# rumpus.net
KiCad netlist of a schematic drawn in EAGLE
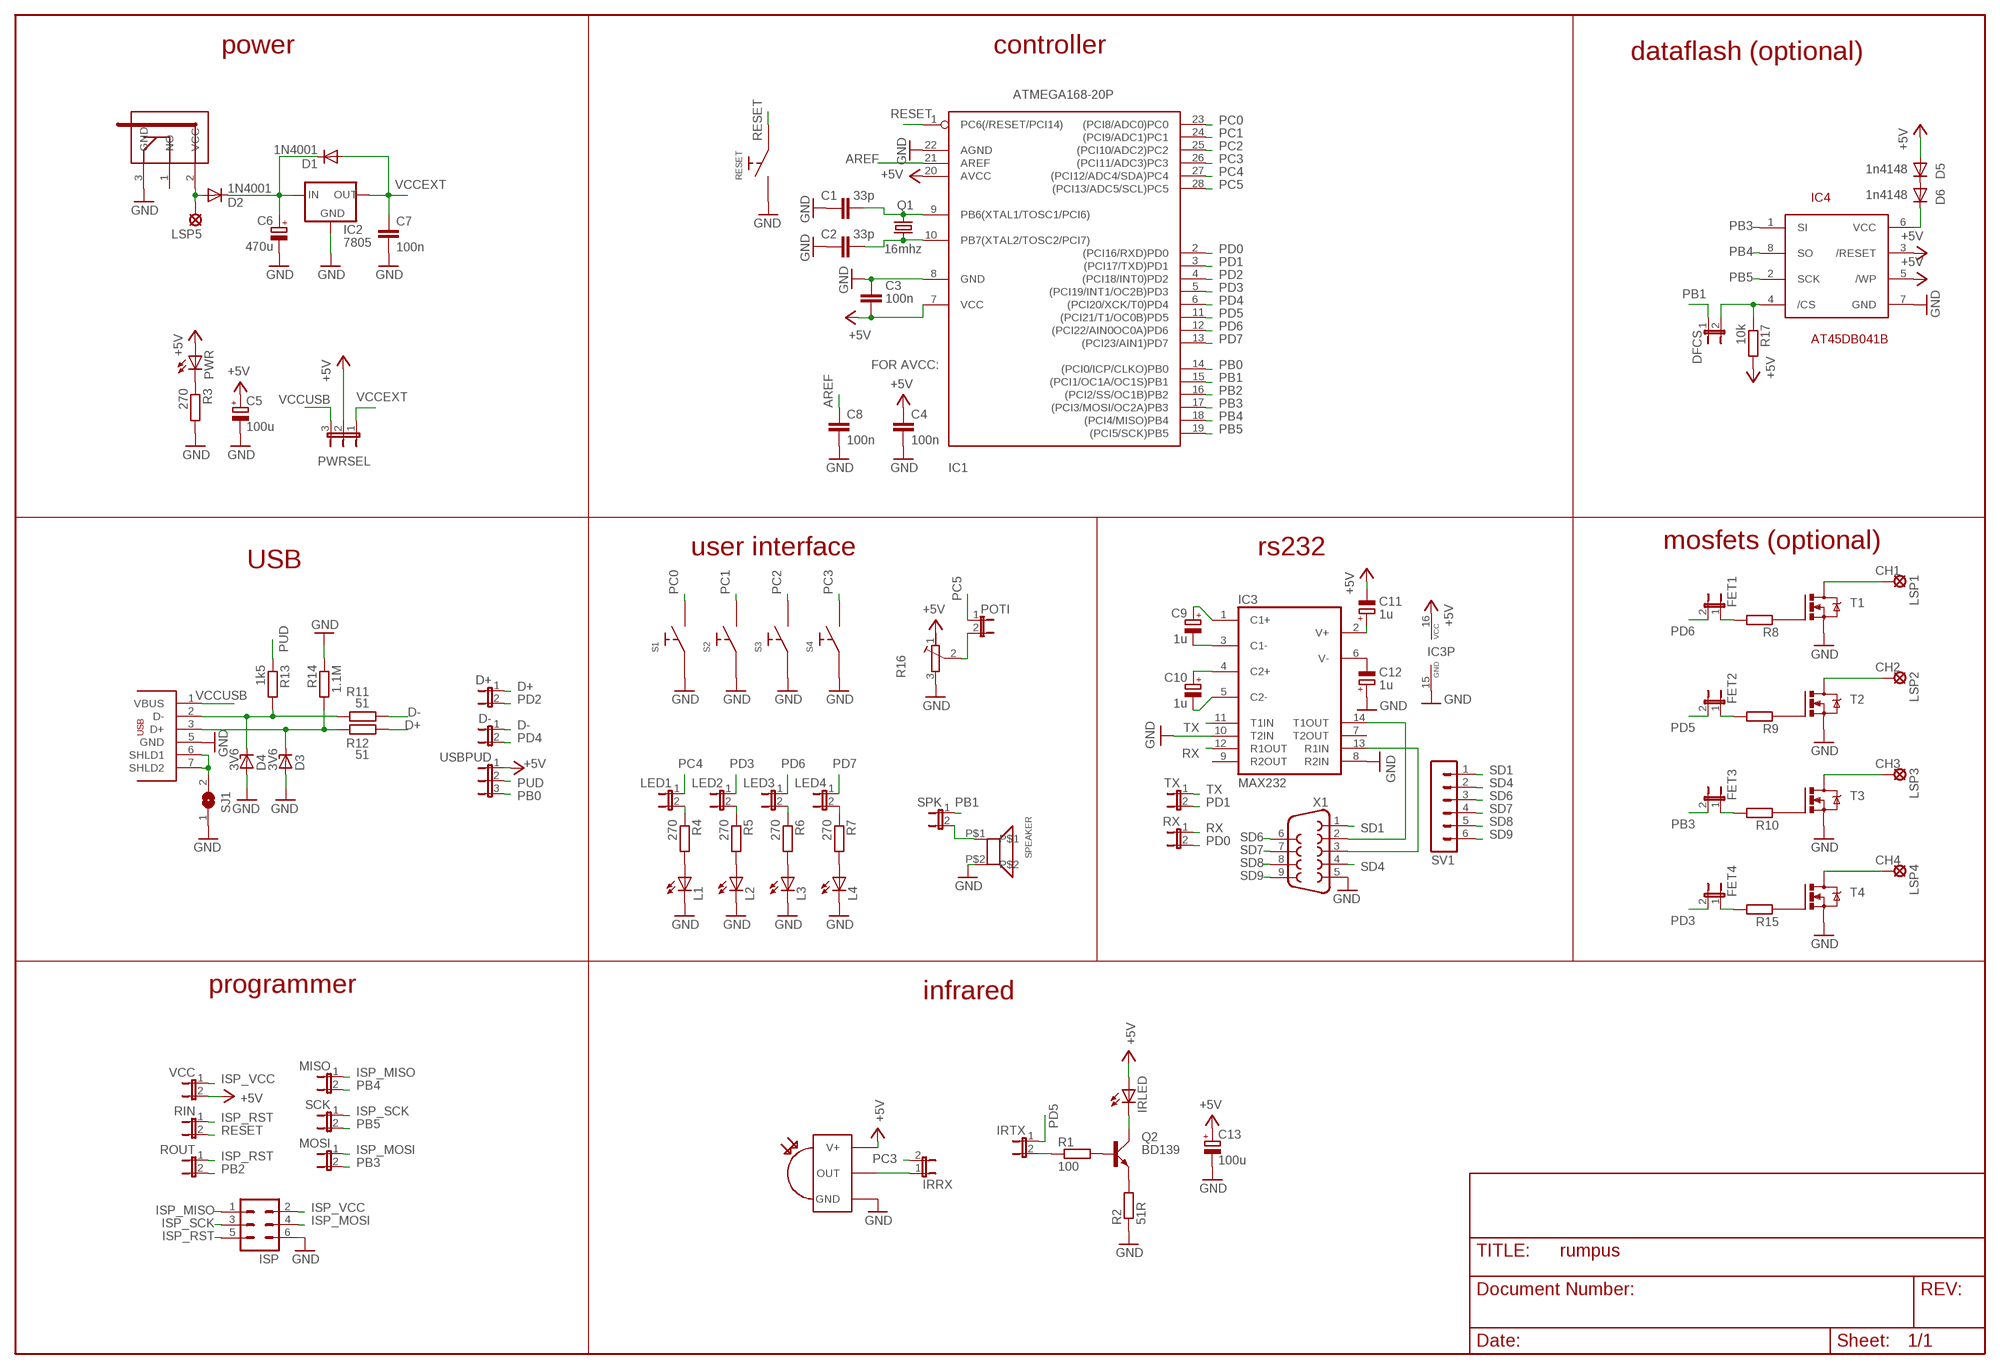
[diagram p0: schematic, sheet 1]

(export (version "E")
  (design (tool "Eeschema 10.0.6"))
  (components
    (comp (ref "C1")
      (value "33p")
      (footprint "eagle-import:C025-024X044")
      (libsource (lib "eagle-import") (part "C-EU025-024X044"))
    )
    (comp (ref "C2")
      (value "33p")
      (footprint "eagle-import:C025-024X044")
      (libsource (lib "eagle-import") (part "C-EU025-024X044"))
    )
    (comp (ref "C3")
      (value "100n")
      (footprint "eagle-import:C025-024X044")
      (libsource (lib "eagle-import") (part "C-EU025-024X044"))
    )
    (comp (ref "C4")
      (value "100n")
      (footprint "eagle-import:C025-024X044")
      (libsource (lib "eagle-import") (part "C-EU025-024X044"))
    )
    (comp (ref "C5")
      (value "100u")
      (footprint "eagle-import:E2,5-6")
      (libsource (lib "eagle-import") (part "CPOL-EUE2.5-6"))
    )
    (comp (ref "C6")
      (value "470u")
      (footprint "eagle-import:E5-10,5")
      (libsource (lib "eagle-import") (part "CPOL-EUE5-10.5"))
    )
    (comp (ref "C7")
      (value "100n")
      (footprint "eagle-import:C025-024X044")
      (libsource (lib "eagle-import") (part "C-EU025-024X044"))
    )
    (comp (ref "C8")
      (value "100n")
      (footprint "eagle-import:C025-024X044")
      (libsource (lib "eagle-import") (part "C-EU025-024X044"))
    )
    (comp (ref "C9")
      (value "1u")
      (footprint "eagle-import:E2,5-6")
      (libsource (lib "eagle-import") (part "CPOL-EUE2.5-6"))
    )
    (comp (ref "C10")
      (value "1u")
      (footprint "eagle-import:E2,5-6")
      (libsource (lib "eagle-import") (part "CPOL-EUE2.5-6"))
    )
    (comp (ref "C11")
      (value "1u")
      (footprint "eagle-import:E2,5-6")
      (libsource (lib "eagle-import") (part "CPOL-EUE2.5-6"))
    )
    (comp (ref "C12")
      (value "1u")
      (footprint "eagle-import:E2,5-6")
      (libsource (lib "eagle-import") (part "CPOL-EUE2.5-6"))
    )
    (comp (ref "C13")
      (value "100u")
      (footprint "eagle-import:E2,5-6")
      (libsource (lib "eagle-import") (part "CPOL-EUE2.5-6"))
    )
    (comp (ref "D+")
      (value "JP1E")
      (footprint "eagle-import:JP1")
      (libsource (lib "eagle-import") (part "JP1E"))
    )
    (comp (ref "D-")
      (value "JP1E")
      (footprint "eagle-import:JP1")
      (libsource (lib "eagle-import") (part "JP1E"))
    )
    (comp (ref "D1")
      (value "1N4001")
      (footprint "eagle-import:DO41-10")
      (libsource (lib "eagle-import") (part "1N4004"))
    )
    (comp (ref "D2")
      (value "1N4001")
      (footprint "eagle-import:DO41-10")
      (libsource (lib "eagle-import") (part "1N4004"))
    )
    (comp (ref "D3")
      (value "3V6")
      (footprint "eagle-import:ZDIO-2.5")
      (libsource (lib "eagle-import") (part "ZENER-DIODEZD-2.5"))
    )
    (comp (ref "D4")
      (value "3V6")
      (footprint "eagle-import:ZDIO-2.5")
      (libsource (lib "eagle-import") (part "ZENER-DIODEZD-2.5"))
    )
    (comp (ref "D5")
      (value "1n4148")
      (footprint "eagle-import:D-2.5")
      (libsource (lib "eagle-import") (part "DIODE-D-2.5"))
    )
    (comp (ref "D6")
      (value "1n4148")
      (footprint "eagle-import:D-2.5")
      (libsource (lib "eagle-import") (part "DIODE-D-2.5"))
    )
    (comp (ref "DFCS")
      (value "JP1E")
      (footprint "eagle-import:JP1")
      (libsource (lib "eagle-import") (part "JP1E"))
    )
    (comp (ref "FET1")
      (value "JP1E")
      (footprint "eagle-import:JP1")
      (libsource (lib "eagle-import") (part "JP1E"))
    )
    (comp (ref "FET2")
      (value "JP1E")
      (footprint "eagle-import:JP1")
      (libsource (lib "eagle-import") (part "JP1E"))
    )
    (comp (ref "FET3")
      (value "JP1E")
      (footprint "eagle-import:JP1")
      (libsource (lib "eagle-import") (part "JP1E"))
    )
    (comp (ref "FET4")
      (value "JP1E")
      (footprint "eagle-import:JP1")
      (libsource (lib "eagle-import") (part "JP1E"))
    )
    (comp (ref "IC1")
      (value "ATMEGA168-20P")
      (footprint "eagle-import:DIL28-3")
      (libsource (lib "eagle-import") (part "ATMEGA168P-20"))
    )
    (comp (ref "IC2")
      (value "7805")
      (footprint "eagle-import:78XXS")
      (libsource (lib "eagle-import") (part "78XXS"))
    )
    (comp (ref "IC3")
      (value "MAX232")
      (footprint "eagle-import:DIL16")
      (libsource (lib "eagle-import") (part "MAX232"))
    )
    (comp (ref "IC4")
      (value "AT45DB041B")
      (footprint "eagle-import:SOIC8")
      (libsource (lib "eagle-import") (part "AT45DB041B"))
    )
    (comp (ref "IRLED")
      (value "LED5MM")
      (footprint "eagle-import:LED5MM")
      (libsource (lib "eagle-import") (part "LED5MM"))
    )
    (comp (ref "IRRX")
      (value "JP1E")
      (footprint "eagle-import:JP1")
      (libsource (lib "eagle-import") (part "JP1E"))
    )
    (comp (ref "IRTX")
      (value "JP1E")
      (footprint "eagle-import:JP1")
      (libsource (lib "eagle-import") (part "JP1E"))
    )
    (comp (ref "ISP")
      (value "MA03-2")
      (footprint "eagle-import:MA03-2")
      (libsource (lib "eagle-import") (part "MA03-2"))
    )
    (comp (ref "L1")
      (value "LED3MM")
      (footprint "eagle-import:LED3MM")
      (libsource (lib "eagle-import") (part "LED3MM"))
    )
    (comp (ref "L2")
      (value "LED3MM")
      (footprint "eagle-import:LED3MM")
      (libsource (lib "eagle-import") (part "LED3MM"))
    )
    (comp (ref "L3")
      (value "LED3MM")
      (footprint "eagle-import:LED3MM")
      (libsource (lib "eagle-import") (part "LED3MM"))
    )
    (comp (ref "L4")
      (value "LED3MM")
      (footprint "eagle-import:LED3MM")
      (libsource (lib "eagle-import") (part "LED3MM"))
    )
    (comp (ref "LED1")
      (value "JP1E")
      (footprint "eagle-import:JP1")
      (libsource (lib "eagle-import") (part "JP1E"))
    )
    (comp (ref "LED2")
      (value "JP1E")
      (footprint "eagle-import:JP1")
      (libsource (lib "eagle-import") (part "JP1E"))
    )
    (comp (ref "LED3")
      (value "JP1E")
      (footprint "eagle-import:JP1")
      (libsource (lib "eagle-import") (part "JP1E"))
    )
    (comp (ref "LED4")
      (value "JP1E")
      (footprint "eagle-import:JP1")
      (libsource (lib "eagle-import") (part "JP1E"))
    )
    (comp (ref "LSP1")
      (value "LSP10")
      (footprint "eagle-import:LSP10")
      (libsource (lib "eagle-import") (part "LSP10"))
    )
    (comp (ref "LSP2")
      (value "LSP10")
      (footprint "eagle-import:LSP10")
      (libsource (lib "eagle-import") (part "LSP10"))
    )
    (comp (ref "LSP3")
      (value "LSP10")
      (footprint "eagle-import:LSP10")
      (libsource (lib "eagle-import") (part "LSP10"))
    )
    (comp (ref "LSP4")
      (value "LSP10")
      (footprint "eagle-import:LSP10")
      (libsource (lib "eagle-import") (part "LSP10"))
    )
    (comp (ref "LSP5")
      (value "LSP10")
      (footprint "eagle-import:LSP10")
      (libsource (lib "eagle-import") (part "LSP10"))
    )
    (comp (ref "MISO")
      (value "JP1E")
      (footprint "eagle-import:JP1")
      (libsource (lib "eagle-import") (part "JP1E"))
    )
    (comp (ref "MOSI")
      (value "JP1E")
      (footprint "eagle-import:JP1")
      (libsource (lib "eagle-import") (part "JP1E"))
    )
    (comp (ref "POTI")
      (value "JP1E")
      (footprint "eagle-import:JP1")
      (libsource (lib "eagle-import") (part "JP1E"))
    )
    (comp (ref "PWR")
      (value "LED3MM")
      (footprint "eagle-import:LED3MM")
      (libsource (lib "eagle-import") (part "LED3MM"))
    )
    (comp (ref "PWRSEL")
      (value "JP2E")
      (footprint "eagle-import:JP2")
      (libsource (lib "eagle-import") (part "JP2E"))
    )
    (comp (ref "Q1")
      (value "16mhz")
      (footprint "eagle-import:HC49U-V")
      (libsource (lib "eagle-import") (part "CRYTALHC49U-V"))
    )
    (comp (ref "Q2")
      (value "BD139")
      (footprint "eagle-import:TO126AV")
      (libsource (lib "eagle-import") (part "BD139"))
    )
    (comp (ref "R1")
      (value "100")
      (footprint "eagle-import:0204V")
      (libsource (lib "eagle-import") (part "R-EU_0204/2V"))
    )
    (comp (ref "R2")
      (value "51R")
      (footprint "eagle-import:0204V")
      (libsource (lib "eagle-import") (part "R-EU_0204/2V"))
    )
    (comp (ref "R3")
      (value "270")
      (footprint "eagle-import:0204_7")
      (libsource (lib "eagle-import") (part "R-EU_0204/7"))
    )
    (comp (ref "R4")
      (value "270")
      (footprint "eagle-import:0204V")
      (libsource (lib "eagle-import") (part "R-EU_0204/2V"))
    )
    (comp (ref "R5")
      (value "270")
      (footprint "eagle-import:0204V")
      (libsource (lib "eagle-import") (part "R-EU_0204/2V"))
    )
    (comp (ref "R6")
      (value "270")
      (footprint "eagle-import:0204V")
      (libsource (lib "eagle-import") (part "R-EU_0204/2V"))
    )
    (comp (ref "R7")
      (value "270")
      (footprint "eagle-import:0204V")
      (libsource (lib "eagle-import") (part "R-EU_0204/2V"))
    )
    (comp (ref "R8")
      (value "R-EU_0204/2V")
      (footprint "eagle-import:0204V")
      (libsource (lib "eagle-import") (part "R-EU_0204/2V"))
    )
    (comp (ref "R9")
      (value "R-EU_0204/2V")
      (footprint "eagle-import:0204V")
      (libsource (lib "eagle-import") (part "R-EU_0204/2V"))
    )
    (comp (ref "R10")
      (value "R-EU_0204/2V")
      (footprint "eagle-import:0204V")
      (libsource (lib "eagle-import") (part "R-EU_0204/2V"))
    )
    (comp (ref "R11")
      (value "51")
      (footprint "eagle-import:0204V")
      (libsource (lib "eagle-import") (part "R-EU_0204/2V"))
    )
    (comp (ref "R12")
      (value "51")
      (footprint "eagle-import:0204V")
      (libsource (lib "eagle-import") (part "R-EU_0204/2V"))
    )
    (comp (ref "R13")
      (value "1k5")
      (footprint "eagle-import:0204V")
      (libsource (lib "eagle-import") (part "R-EU_0204/2V"))
    )
    (comp (ref "R14")
      (value "1.1M")
      (footprint "eagle-import:0204V")
      (libsource (lib "eagle-import") (part "R-EU_0204/2V"))
    )
    (comp (ref "R15")
      (value "R-EU_0204/2V")
      (footprint "eagle-import:0204V")
      (libsource (lib "eagle-import") (part "R-EU_0204/2V"))
    )
    (comp (ref "R16")
      (value "R-TRIMMPT6-L")
      (footprint "eagle-import:PT6-L")
      (libsource (lib "eagle-import") (part "R-TRIMMPT6-L"))
    )
    (comp (ref "R17")
      (value "10k")
      (footprint "eagle-import:0204V")
      (libsource (lib "eagle-import") (part "R-EU_0204/2V"))
    )
    (comp (ref "RESET")
      (value "MIKROTASTER6X6L")
      (footprint "eagle-import:TASTER3301")
      (libsource (lib "eagle-import") (part "MIKROTASTER6X6L"))
    )
    (comp (ref "RIN")
      (value "JP1E")
      (footprint "eagle-import:JP1")
      (libsource (lib "eagle-import") (part "JP1E"))
    )
    (comp (ref "ROUT")
      (value "JP1E")
      (footprint "eagle-import:JP1")
      (libsource (lib "eagle-import") (part "JP1E"))
    )
    (comp (ref "RX")
      (value "JP1E")
      (footprint "eagle-import:JP1")
      (libsource (lib "eagle-import") (part "JP1E"))
    )
    (comp (ref "S1")
      (value "MIKROTASTER6X6L")
      (footprint "eagle-import:TASTER3301")
      (libsource (lib "eagle-import") (part "MIKROTASTER6X6L"))
    )
    (comp (ref "S2")
      (value "MIKROTASTER6X6L")
      (footprint "eagle-import:TASTER3301")
      (libsource (lib "eagle-import") (part "MIKROTASTER6X6L"))
    )
    (comp (ref "S3")
      (value "MIKROTASTER6X6L")
      (footprint "eagle-import:TASTER3301")
      (libsource (lib "eagle-import") (part "MIKROTASTER6X6L"))
    )
    (comp (ref "S4")
      (value "MIKROTASTER6X6L")
      (footprint "eagle-import:TASTER3301")
      (libsource (lib "eagle-import") (part "MIKROTASTER6X6L"))
    )
    (comp (ref "SCK")
      (value "JP1E")
      (footprint "eagle-import:JP1")
      (libsource (lib "eagle-import") (part "JP1E"))
    )
    (comp (ref "SJ1") (value "SJ") (footprint "eagle-import:SJ") (libsource (lib "eagle-import") (part "SJ")))
    (comp (ref "SPEAKER")
      (value "BUZZER")
      (footprint "eagle-import:BUZZER")
      (libsource (lib "eagle-import") (part "BUZZER"))
    )
    (comp (ref "SPK")
      (value "JP1E")
      (footprint "eagle-import:JP1")
      (libsource (lib "eagle-import") (part "JP1E"))
    )
    (comp (ref "SV1")
      (value "MA06-1")
      (footprint "eagle-import:MA06-1")
      (libsource (lib "eagle-import") (part "MA06-1"))
    )
    (comp (ref "T1")
      (value "N-CHANNEL-MOSFET")
      (footprint "eagle-import:TO220BV")
      (libsource (lib "eagle-import") (part "N-CHANNEL-MOSFET"))
    )
    (comp (ref "T2")
      (value "N-CHANNEL-MOSFET")
      (footprint "eagle-import:TO220BV")
      (libsource (lib "eagle-import") (part "N-CHANNEL-MOSFET"))
    )
    (comp (ref "T3")
      (value "N-CHANNEL-MOSFET")
      (footprint "eagle-import:TO220BV")
      (libsource (lib "eagle-import") (part "N-CHANNEL-MOSFET"))
    )
    (comp (ref "T4")
      (value "N-CHANNEL-MOSFET")
      (footprint "eagle-import:TO220BV")
      (libsource (lib "eagle-import") (part "N-CHANNEL-MOSFET"))
    )
    (comp (ref "TX")
      (value "JP1E")
      (footprint "eagle-import:JP1")
      (libsource (lib "eagle-import") (part "JP1E"))
    )
    (comp (ref "U$2")
      (value "TSOP1738")
      (footprint "eagle-import:TSOP17XX")
      (libsource (lib "eagle-import") (part "TSOP1738"))
    )
    (comp (ref "U$3")
      (value "HEBW21")
      (footprint "eagle-import:HEBW21")
      (libsource (lib "eagle-import") (part "HEBW21"))
    )
    (comp (ref "USB")
      (value "USB-SOCKETMINI-B")
      (footprint "eagle-import:USB-BWM")
      (libsource (lib "eagle-import") (part "USB-SOCKETMINI-B"))
    )
    (comp (ref "USBPUD")
      (value "JP2E")
      (footprint "eagle-import:JP2")
      (libsource (lib "eagle-import") (part "JP2E"))
    )
    (comp (ref "VCC")
      (value "JP1E")
      (footprint "eagle-import:JP1")
      (libsource (lib "eagle-import") (part "JP1E"))
    )
    (comp (ref "X1")
      (value "F09HP")
      (footprint "eagle-import:F09HP")
      (libsource (lib "eagle-import") (part "F09HP"))
    )
  )
  (nets
    (net (code "1") (name "+5V") (class "Default")
      (node (ref "C11") (pin "-") (pinfunction "-_-") (pintype "passive"))
      (node (ref "C13") (pin "+") (pinfunction "+_+") (pintype "passive"))
      (node (ref "C3") (pin "2") (pinfunction "2_2") (pintype "passive"))
      (node (ref "C4") (pin "1") (pinfunction "1_1") (pintype "passive"))
      (node (ref "C5") (pin "+") (pinfunction "+_+") (pintype "passive"))
      (node (ref "D5") (pin "A") (pinfunction "A_A") (pintype "passive"))
      (node (ref "IC1") (pin "20") (pinfunction "AVCC_20") (pintype "bidirectional"))
      (node (ref "IC1") (pin "7") (pinfunction "VCC_7") (pintype "bidirectional"))
      (node (ref "IC3") (pin "16") (pinfunction "VCC_16") (pintype "power_in"))
      (node (ref "IC4") (pin "3") (pinfunction "/RESET_3") (pintype "bidirectional"))
      (node (ref "IC4") (pin "5") (pinfunction "/WP_5") (pintype "bidirectional"))
      (node (ref "IRLED") (pin "A") (pinfunction "A_A") (pintype "passive"))
      (node (ref "PWR") (pin "A") (pinfunction "A_A") (pintype "passive"))
      (node (ref "PWRSEL") (pin "2") (pinfunction "2_2") (pintype "passive"))
      (node (ref "R16") (pin "1") (pinfunction "A_1") (pintype "passive"))
      (node (ref "R17") (pin "2") (pinfunction "2_2") (pintype "passive"))
      (node (ref "U$2") (pin "V+") (pinfunction "V+_V+") (pintype "bidirectional"))
      (node (ref "USBPUD") (pin "1") (pinfunction "1_1") (pintype "passive"))
      (node (ref "VCC") (pin "2") (pinfunction "2_2") (pintype "passive"))
    )
    (net (code "2") (name "/AREF") (class "Default")
      (node (ref "C8") (pin "1") (pinfunction "1_1") (pintype "passive"))
      (node (ref "IC1") (pin "21") (pinfunction "AREF_21") (pintype "bidirectional"))
    )
    (net (code "3") (name "/CH1") (class "Default")
      (node (ref "LSP1") (pin "MP") (pinfunction "MP_MP") (pintype "passive"))
      (node (ref "T1") (pin "D") (pinfunction "D_D") (pintype "passive"))
    )
    (net (code "4") (name "/CH2") (class "Default")
      (node (ref "LSP2") (pin "MP") (pinfunction "MP_MP") (pintype "passive"))
      (node (ref "T2") (pin "D") (pinfunction "D_D") (pintype "passive"))
    )
    (net (code "5") (name "/CH3") (class "Default")
      (node (ref "LSP3") (pin "MP") (pinfunction "MP_MP") (pintype "passive"))
      (node (ref "T3") (pin "D") (pinfunction "D_D") (pintype "passive"))
    )
    (net (code "6") (name "/CH4") (class "Default")
      (node (ref "LSP4") (pin "MP") (pinfunction "MP_MP") (pintype "passive"))
      (node (ref "T4") (pin "D") (pinfunction "D_D") (pintype "passive"))
    )
    (net (code "7") (name "/D+") (class "Default")
      (node (ref "D+") (pin "1") (pinfunction "1_1") (pintype "passive"))
      (node (ref "R12") (pin "2") (pinfunction "2_2") (pintype "passive"))
    )
    (net (code "8") (name "/D-") (class "Default")
      (node (ref "D-") (pin "1") (pinfunction "1_1") (pintype "passive"))
      (node (ref "R11") (pin "2") (pinfunction "2_2") (pintype "passive"))
    )
    (net (code "9") (name "/ISP_MISO") (class "Default")
      (node (ref "ISP") (pin "1") (pinfunction "1_1") (pintype "passive"))
      (node (ref "MISO") (pin "1") (pinfunction "1_1") (pintype "passive"))
    )
    (net (code "10") (name "/ISP_MOSI") (class "Default")
      (node (ref "ISP") (pin "4") (pinfunction "4_4") (pintype "passive"))
      (node (ref "MOSI") (pin "1") (pinfunction "1_1") (pintype "passive"))
    )
    (net (code "11") (name "/ISP_RST") (class "Default")
      (node (ref "ISP") (pin "5") (pinfunction "5_5") (pintype "passive"))
      (node (ref "RIN") (pin "1") (pinfunction "1_1") (pintype "passive"))
      (node (ref "ROUT") (pin "1") (pinfunction "1_1") (pintype "passive"))
    )
    (net (code "12") (name "/ISP_SCK") (class "Default")
      (node (ref "ISP") (pin "3") (pinfunction "3_3") (pintype "passive"))
      (node (ref "SCK") (pin "1") (pinfunction "1_1") (pintype "passive"))
    )
    (net (code "13") (name "/ISP_VCC") (class "Default")
      (node (ref "ISP") (pin "2") (pinfunction "2_2") (pintype "passive"))
      (node (ref "VCC") (pin "1") (pinfunction "1_1") (pintype "passive"))
    )
    (net (code "14") (name "/PB0") (class "Default")
      (node (ref "IC1") (pin "14") (pinfunction "(PCI0/ICP/CLKO)PB0_14") (pintype "bidirectional"))
      (node (ref "USBPUD") (pin "3") (pinfunction "3_3") (pintype "passive"))
    )
    (net (code "15") (name "/PB1") (class "Default")
      (node (ref "DFCS") (pin "1") (pinfunction "1_1") (pintype "passive"))
      (node (ref "IC1") (pin "15") (pinfunction "(PCI1/OC1A/OC1S)PB1_15") (pintype "bidirectional"))
      (node (ref "SPK") (pin "1") (pinfunction "1_1") (pintype "passive"))
    )
    (net (code "16") (name "/PB2") (class "Default")
      (node (ref "IC1") (pin "16") (pinfunction "(PCI2/SS/OC1B)PB2_16") (pintype "bidirectional"))
      (node (ref "ROUT") (pin "2") (pinfunction "2_2") (pintype "passive"))
    )
    (net (code "17") (name "/PB3") (class "Default")
      (node (ref "FET3") (pin "2") (pinfunction "2_2") (pintype "passive"))
      (node (ref "IC1") (pin "17") (pinfunction "(PCI3/MOSI/OC2A)PB3_17") (pintype "bidirectional"))
      (node (ref "IC4") (pin "1") (pinfunction "SI_1") (pintype "bidirectional"))
      (node (ref "MOSI") (pin "2") (pinfunction "2_2") (pintype "passive"))
    )
    (net (code "18") (name "/PB4") (class "Default")
      (node (ref "IC1") (pin "18") (pinfunction "(PCI4/MISO)PB4_18") (pintype "bidirectional"))
      (node (ref "IC4") (pin "8") (pinfunction "SO_8") (pintype "bidirectional"))
      (node (ref "MISO") (pin "2") (pinfunction "2_2") (pintype "passive"))
    )
    (net (code "19") (name "/PB5") (class "Default")
      (node (ref "IC1") (pin "19") (pinfunction "(PCI5/SCK)PB5_19") (pintype "bidirectional"))
      (node (ref "IC4") (pin "2") (pinfunction "SCK_2") (pintype "bidirectional"))
      (node (ref "SCK") (pin "2") (pinfunction "2_2") (pintype "passive"))
    )
    (net (code "20") (name "/PC0") (class "Default")
      (node (ref "IC1") (pin "23") (pinfunction "(PCI8/ADC0)PC0_23") (pintype "bidirectional"))
      (node (ref "S1") (pin "2") (pinfunction "2_2") (pintype "passive"))
    )
    (net (code "21") (name "/PC1") (class "Default")
      (node (ref "IC1") (pin "24") (pinfunction "(PCI9/ADC1)PC1_24") (pintype "bidirectional"))
      (node (ref "S2") (pin "2") (pinfunction "2_2") (pintype "passive"))
    )
    (net (code "22") (name "/PC2") (class "Default")
      (node (ref "IC1") (pin "25") (pinfunction "(PCI10/ADC2)PC2_25") (pintype "bidirectional"))
      (node (ref "S3") (pin "2") (pinfunction "2_2") (pintype "passive"))
    )
    (net (code "23") (name "/PC3") (class "Default")
      (node (ref "IC1") (pin "26") (pinfunction "(PCI11/ADC3)PC3_26") (pintype "bidirectional"))
      (node (ref "IRRX") (pin "2") (pinfunction "2_2") (pintype "passive"))
      (node (ref "S4") (pin "2") (pinfunction "2_2") (pintype "passive"))
    )
    (net (code "24") (name "/PC4") (class "Default")
      (node (ref "IC1") (pin "27") (pinfunction "(PCI12/ADC4/SDA)PC4_27") (pintype "bidirectional"))
      (node (ref "LED1") (pin "1") (pinfunction "1_1") (pintype "passive"))
    )
    (net (code "25") (name "/PC5") (class "Default")
      (node (ref "IC1") (pin "28") (pinfunction "(PCI13/ADC5/SCL)PC5_28") (pintype "bidirectional"))
      (node (ref "POTI") (pin "1") (pinfunction "1_1") (pintype "passive"))
    )
    (net (code "26") (name "/PD0") (class "Default")
      (node (ref "IC1") (pin "2") (pinfunction "(PCI16/RXD)PD0_2") (pintype "bidirectional"))
      (node (ref "RX") (pin "2") (pinfunction "2_2") (pintype "passive"))
    )
    (net (code "27") (name "/PD1") (class "Default")
      (node (ref "IC1") (pin "3") (pinfunction "(PCI17/TXD)PD1_3") (pintype "bidirectional"))
      (node (ref "TX") (pin "2") (pinfunction "2_2") (pintype "passive"))
    )
    (net (code "28") (name "/PD2") (class "Default")
      (node (ref "D+") (pin "2") (pinfunction "2_2") (pintype "passive"))
      (node (ref "IC1") (pin "4") (pinfunction "(PCI18/INT0)PD2_4") (pintype "bidirectional"))
    )
    (net (code "29") (name "/PD3") (class "Default")
      (node (ref "FET4") (pin "2") (pinfunction "2_2") (pintype "passive"))
      (node (ref "IC1") (pin "5") (pinfunction "(PCI19/INT1/OC2B)PD3_5") (pintype "bidirectional"))
      (node (ref "LED2") (pin "1") (pinfunction "1_1") (pintype "passive"))
    )
    (net (code "30") (name "/PD4") (class "Default")
      (node (ref "D-") (pin "2") (pinfunction "2_2") (pintype "passive"))
      (node (ref "IC1") (pin "6") (pinfunction "(PCI20/XCK/T0)PD4_6") (pintype "bidirectional"))
    )
    (net (code "31") (name "/PD5") (class "Default")
      (node (ref "FET2") (pin "2") (pinfunction "2_2") (pintype "passive"))
      (node (ref "IC1") (pin "11") (pinfunction "(PCI21/T1/OC0B)PD5_11") (pintype "bidirectional"))
      (node (ref "IRTX") (pin "1") (pinfunction "1_1") (pintype "passive"))
    )
    (net (code "32") (name "/PD6") (class "Default")
      (node (ref "FET1") (pin "2") (pinfunction "2_2") (pintype "passive"))
      (node (ref "IC1") (pin "12") (pinfunction "(PCI22/AIN0OC0A)PD6_12") (pintype "bidirectional"))
      (node (ref "LED3") (pin "1") (pinfunction "1_1") (pintype "passive"))
    )
    (net (code "33") (name "/PD7") (class "Default")
      (node (ref "IC1") (pin "13") (pinfunction "(PCI23/AIN1)PD7_13") (pintype "bidirectional"))
      (node (ref "LED4") (pin "1") (pinfunction "1_1") (pintype "passive"))
    )
    (net (code "34") (name "/PUD") (class "Default")
      (node (ref "R13") (pin "1") (pinfunction "1_1") (pintype "passive"))
      (node (ref "USBPUD") (pin "2") (pinfunction "2_2") (pintype "passive"))
    )
    (net (code "35") (name "/RESET") (class "Default")
      (node (ref "IC1") (pin "1") (pinfunction "PC6(/RESET/PCI14)_1") (pintype "bidirectional"))
      (node (ref "RESET") (pin "1") (pinfunction "1_1") (pintype "passive"))
      (node (ref "RIN") (pin "2") (pinfunction "2_2") (pintype "passive"))
    )
    (net (code "36") (name "/RX") (class "Default")
      (node (ref "IC3") (pin "12") (pinfunction "R1OUT_12") (pintype "output"))
      (node (ref "RX") (pin "1") (pinfunction "1_1") (pintype "passive"))
    )
    (net (code "37") (name "/SD1") (class "Default")
      (node (ref "SV1") (pin "1") (pinfunction "1_1") (pintype "passive"))
      (node (ref "X1") (pin "1") (pinfunction "1_1") (pintype "passive"))
    )
    (net (code "38") (name "/SD4") (class "Default")
      (node (ref "SV1") (pin "2") (pinfunction "2_2") (pintype "passive"))
      (node (ref "X1") (pin "4") (pinfunction "4_4") (pintype "passive"))
    )
    (net (code "39") (name "/SD6") (class "Default")
      (node (ref "SV1") (pin "3") (pinfunction "3_3") (pintype "passive"))
      (node (ref "X1") (pin "6") (pinfunction "6_6") (pintype "passive"))
    )
    (net (code "40") (name "/SD7") (class "Default")
      (node (ref "SV1") (pin "4") (pinfunction "4_4") (pintype "passive"))
      (node (ref "X1") (pin "7") (pinfunction "7_7") (pintype "passive"))
    )
    (net (code "41") (name "/SD8") (class "Default")
      (node (ref "SV1") (pin "5") (pinfunction "5_5") (pintype "passive"))
      (node (ref "X1") (pin "8") (pinfunction "8_8") (pintype "passive"))
    )
    (net (code "42") (name "/SD9") (class "Default")
      (node (ref "SV1") (pin "6") (pinfunction "6_6") (pintype "passive"))
      (node (ref "X1") (pin "9") (pinfunction "9_9") (pintype "passive"))
    )
    (net (code "43") (name "/TX") (class "Default")
      (node (ref "IC3") (pin "11") (pinfunction "T1IN_11") (pintype "input"))
      (node (ref "TX") (pin "1") (pinfunction "1_1") (pintype "passive"))
    )
    (net (code "44") (name "/VCCEXT") (class "Default")
      (node (ref "C7") (pin "1") (pinfunction "1_1") (pintype "passive"))
      (node (ref "D1") (pin "A") (pinfunction "A_A") (pintype "passive"))
      (node (ref "IC2") (pin "OUT") (pinfunction "OUT_OUT") (pintype "passive"))
      (node (ref "PWRSEL") (pin "1") (pinfunction "1_1") (pintype "passive"))
    )
    (net (code "45") (name "/VCCUSB") (class "Default")
      (node (ref "PWRSEL") (pin "3") (pinfunction "3_3") (pintype "passive"))
      (node (ref "USB") (pin "1") (pinfunction "VBUS_1") (pintype "passive"))
    )
    (net (code "46") (name "GND") (class "Default")
      (node (ref "C1") (pin "2") (pinfunction "2_2") (pintype "passive"))
      (node (ref "C12") (pin "+") (pinfunction "+_+") (pintype "passive"))
      (node (ref "C13") (pin "-") (pinfunction "-_-") (pintype "passive"))
      (node (ref "C2") (pin "2") (pinfunction "2_2") (pintype "passive"))
      (node (ref "C3") (pin "1") (pinfunction "1_1") (pintype "passive"))
      (node (ref "C4") (pin "2") (pinfunction "2_2") (pintype "passive"))
      (node (ref "C5") (pin "-") (pinfunction "-_-") (pintype "passive"))
      (node (ref "C6") (pin "-") (pinfunction "-_-") (pintype "passive"))
      (node (ref "C7") (pin "2") (pinfunction "2_2") (pintype "passive"))
      (node (ref "C8") (pin "2") (pinfunction "2_2") (pintype "passive"))
      (node (ref "D3") (pin "A") (pinfunction "A_A") (pintype "passive"))
      (node (ref "D4") (pin "A") (pinfunction "A_A") (pintype "passive"))
      (node (ref "IC1") (pin "22") (pinfunction "AGND_22") (pintype "bidirectional"))
      (node (ref "IC1") (pin "8") (pinfunction "GND_8") (pintype "bidirectional"))
      (node (ref "IC2") (pin "GND") (pinfunction "GND_GND") (pintype "input"))
      (node (ref "IC3") (pin "10") (pinfunction "T2IN_10") (pintype "input"))
      (node (ref "IC3") (pin "15") (pinfunction "GND_15") (pintype "power_in"))
      (node (ref "IC3") (pin "8") (pinfunction "R2IN_8") (pintype "input"))
      (node (ref "IC4") (pin "7") (pinfunction "GND_7") (pintype "bidirectional"))
      (node (ref "ISP") (pin "6") (pinfunction "6_6") (pintype "passive"))
      (node (ref "L1") (pin "K") (pinfunction "C_K") (pintype "passive"))
      (node (ref "L2") (pin "K") (pinfunction "C_K") (pintype "passive"))
      (node (ref "L3") (pin "K") (pinfunction "C_K") (pintype "passive"))
      (node (ref "L4") (pin "K") (pinfunction "C_K") (pintype "passive"))
      (node (ref "R14") (pin "1") (pinfunction "1_1") (pintype "passive"))
      (node (ref "R16") (pin "3") (pinfunction "E_3") (pintype "passive"))
      (node (ref "R2") (pin "1") (pinfunction "1_1") (pintype "passive"))
      (node (ref "R3") (pin "2") (pinfunction "2_2") (pintype "passive"))
      (node (ref "RESET") (pin "2") (pinfunction "2_2") (pintype "passive"))
      (node (ref "S1") (pin "1") (pinfunction "1_1") (pintype "passive"))
      (node (ref "S2") (pin "1") (pinfunction "1_1") (pintype "passive"))
      (node (ref "S3") (pin "1") (pinfunction "1_1") (pintype "passive"))
      (node (ref "S4") (pin "1") (pinfunction "1_1") (pintype "passive"))
      (node (ref "SJ1") (pin "1") (pinfunction "1_1") (pintype "passive"))
      (node (ref "SPEAKER") (pin "P$2") (pinfunction "P$2_P$2") (pintype "bidirectional"))
      (node (ref "T1") (pin "S") (pinfunction "S_S") (pintype "passive"))
      (node (ref "T2") (pin "S") (pinfunction "S_S") (pintype "passive"))
      (node (ref "T3") (pin "S") (pinfunction "S_S") (pintype "passive"))
      (node (ref "T4") (pin "S") (pinfunction "S_S") (pintype "passive"))
      (node (ref "U$2") (pin "GND") (pinfunction "GND_GND") (pintype "bidirectional"))
      (node (ref "U$3") (pin "3") (pinfunction "GND_3") (pintype "bidirectional"))
      (node (ref "USB") (pin "5") (pinfunction "GND_5") (pintype "passive"))
      (node (ref "X1") (pin "5") (pinfunction "5_5") (pintype "passive"))
    )
    (net (code "47") (name "Net-(C6-Pad+)") (class "Default")
      (node (ref "C6") (pin "+") (pinfunction "+_+") (pintype "passive"))
      (node (ref "D1") (pin "C") (pinfunction "C_C") (pintype "passive"))
      (node (ref "D2") (pin "C") (pinfunction "C_C") (pintype "passive"))
      (node (ref "IC2") (pin "IN") (pinfunction "IN_IN") (pintype "input"))
    )
    (net (code "48") (name "Net-(D5-PadC)") (class "Default")
      (node (ref "D5") (pin "C") (pinfunction "C_C") (pintype "passive"))
      (node (ref "D6") (pin "A") (pinfunction "A_A") (pintype "passive"))
    )
    (net (code "49") (name "Net-(FET1-Pad1)") (class "Default")
      (node (ref "FET1") (pin "1") (pinfunction "1_1") (pintype "passive"))
      (node (ref "R8") (pin "2") (pinfunction "2_2") (pintype "passive"))
    )
    (net (code "50") (name "Net-(FET2-Pad1)") (class "Default")
      (node (ref "FET2") (pin "1") (pinfunction "1_1") (pintype "passive"))
      (node (ref "R9") (pin "2") (pinfunction "2_2") (pintype "passive"))
    )
    (net (code "51") (name "Net-(FET3-Pad1)") (class "Default")
      (node (ref "FET3") (pin "1") (pinfunction "1_1") (pintype "passive"))
      (node (ref "R10") (pin "2") (pinfunction "2_2") (pintype "passive"))
    )
    (net (code "52") (name "Net-(FET4-Pad1)") (class "Default")
      (node (ref "FET4") (pin "1") (pinfunction "1_1") (pintype "passive"))
      (node (ref "R15") (pin "2") (pinfunction "2_2") (pintype "passive"))
    )
    (net (code "53") (name "Net-(IC1-PB6(XTAL1{slash}TOSC1{slash}PCI6))") (class "Default")
      (node (ref "C1") (pin "1") (pinfunction "1_1") (pintype "passive"))
      (node (ref "IC1") (pin "9") (pinfunction "PB6(XTAL1/TOSC1/PCI6)_9") (pintype "bidirectional"))
      (node (ref "Q1") (pin "1") (pinfunction "1_1") (pintype "passive"))
    )
    (net (code "54") (name "Net-(IC1-PB7(XTAL2{slash}TOSC2{slash}PCI7))") (class "Default")
      (node (ref "C2") (pin "1") (pinfunction "1_1") (pintype "passive"))
      (node (ref "IC1") (pin "10") (pinfunction "PB7(XTAL2/TOSC2/PCI7)_10") (pintype "bidirectional"))
      (node (ref "Q1") (pin "2") (pinfunction "2_2") (pintype "passive"))
    )
    (net (code "55") (name "Net-(IC3A-C1+)") (class "Default")
      (node (ref "C9") (pin "+") (pinfunction "+_+") (pintype "passive"))
      (node (ref "IC3") (pin "1") (pinfunction "C1+_1") (pintype "bidirectional"))
    )
    (net (code "56") (name "Net-(IC3A-C1-)") (class "Default")
      (node (ref "C9") (pin "-") (pinfunction "-_-") (pintype "passive"))
      (node (ref "IC3") (pin "3") (pinfunction "C1-_3") (pintype "bidirectional"))
    )
    (net (code "57") (name "Net-(IC3A-C2+)") (class "Default")
      (node (ref "C10") (pin "+") (pinfunction "+_+") (pintype "passive"))
      (node (ref "IC3") (pin "4") (pinfunction "C2+_4") (pintype "bidirectional"))
    )
    (net (code "58") (name "Net-(IC3A-C2-)") (class "Default")
      (node (ref "C10") (pin "-") (pinfunction "-_-") (pintype "passive"))
      (node (ref "IC3") (pin "5") (pinfunction "C2-_5") (pintype "bidirectional"))
    )
    (net (code "59") (name "Net-(IC3A-R1IN)") (class "Default")
      (node (ref "IC3") (pin "13") (pinfunction "R1IN_13") (pintype "input"))
      (node (ref "X1") (pin "3") (pinfunction "3_3") (pintype "passive"))
    )
    (net (code "60") (name "Net-(IC3A-T1OUT)") (class "Default")
      (node (ref "IC3") (pin "14") (pinfunction "T1OUT_14") (pintype "output"))
      (node (ref "X1") (pin "2") (pinfunction "2_2") (pintype "passive"))
    )
    (net (code "61") (name "Net-(IC3A-V+)") (class "Default")
      (node (ref "C11") (pin "+") (pinfunction "+_+") (pintype "passive"))
      (node (ref "IC3") (pin "2") (pinfunction "V+_2") (pintype "bidirectional"))
    )
    (net (code "62") (name "Net-(IC3A-V-)") (class "Default")
      (node (ref "C12") (pin "-") (pinfunction "-_-") (pintype "passive"))
      (node (ref "IC3") (pin "6") (pinfunction "V-_6") (pintype "bidirectional"))
    )
    (net (code "63") (name "Net-(IC4-VCC)") (class "Default")
      (node (ref "D6") (pin "C") (pinfunction "C_C") (pintype "passive"))
      (node (ref "IC4") (pin "6") (pinfunction "VCC_6") (pintype "bidirectional"))
    )
    (net (code "64") (name "Net-(IC4-{slash}CS)") (class "Default")
      (node (ref "DFCS") (pin "2") (pinfunction "2_2") (pintype "passive"))
      (node (ref "IC4") (pin "4") (pinfunction "/CS_4") (pintype "bidirectional"))
      (node (ref "R17") (pin "1") (pinfunction "1_1") (pintype "passive"))
    )
    (net (code "65") (name "Net-(IRLED-C)") (class "Default")
      (node (ref "IRLED") (pin "K") (pinfunction "C_K") (pintype "passive"))
      (node (ref "Q2") (pin "C") (pinfunction "C_C") (pintype "passive"))
    )
    (net (code "66") (name "Net-(IRRX-Pad1)") (class "Default")
      (node (ref "IRRX") (pin "1") (pinfunction "1_1") (pintype "passive"))
      (node (ref "U$2") (pin "OUT") (pinfunction "OUT_OUT") (pintype "bidirectional"))
    )
    (net (code "67") (name "Net-(IRTX-Pad2)") (class "Default")
      (node (ref "IRTX") (pin "2") (pinfunction "2_2") (pintype "passive"))
      (node (ref "R1") (pin "1") (pinfunction "1_1") (pintype "passive"))
    )
    (net (code "68") (name "Net-(L1-PadA)") (class "Default")
      (node (ref "L1") (pin "A") (pinfunction "A_A") (pintype "passive"))
      (node (ref "R4") (pin "2") (pinfunction "2_2") (pintype "passive"))
    )
    (net (code "69") (name "Net-(L2-PadA)") (class "Default")
      (node (ref "L2") (pin "A") (pinfunction "A_A") (pintype "passive"))
      (node (ref "R5") (pin "2") (pinfunction "2_2") (pintype "passive"))
    )
    (net (code "70") (name "Net-(L3-PadA)") (class "Default")
      (node (ref "L3") (pin "A") (pinfunction "A_A") (pintype "passive"))
      (node (ref "R6") (pin "2") (pinfunction "2_2") (pintype "passive"))
    )
    (net (code "71") (name "Net-(L4-PadA)") (class "Default")
      (node (ref "L4") (pin "A") (pinfunction "A_A") (pintype "passive"))
      (node (ref "R7") (pin "2") (pinfunction "2_2") (pintype "passive"))
    )
    (net (code "72") (name "Net-(LED1-Pad2)") (class "Default")
      (node (ref "LED1") (pin "2") (pinfunction "2_2") (pintype "passive"))
      (node (ref "R4") (pin "1") (pinfunction "1_1") (pintype "passive"))
    )
    (net (code "73") (name "Net-(LED2-Pad2)") (class "Default")
      (node (ref "LED2") (pin "2") (pinfunction "2_2") (pintype "passive"))
      (node (ref "R5") (pin "1") (pinfunction "1_1") (pintype "passive"))
    )
    (net (code "74") (name "Net-(LED3-Pad2)") (class "Default")
      (node (ref "LED3") (pin "2") (pinfunction "2_2") (pintype "passive"))
      (node (ref "R6") (pin "1") (pinfunction "1_1") (pintype "passive"))
    )
    (net (code "75") (name "Net-(LED4-Pad2)") (class "Default")
      (node (ref "LED4") (pin "2") (pinfunction "2_2") (pintype "passive"))
      (node (ref "R7") (pin "1") (pinfunction "1_1") (pintype "passive"))
    )
    (net (code "76") (name "Net-(PWR-C)") (class "Default")
      (node (ref "PWR") (pin "K") (pinfunction "C_K") (pintype "passive"))
      (node (ref "R3") (pin "1") (pinfunction "1_1") (pintype "passive"))
    )
    (net (code "77") (name "Net-(Q2-PadB)") (class "Default")
      (node (ref "Q2") (pin "B") (pinfunction "B_B") (pintype "passive"))
      (node (ref "R1") (pin "2") (pinfunction "2_2") (pintype "passive"))
    )
    (net (code "78") (name "Net-(Q2-PadE)") (class "Default")
      (node (ref "Q2") (pin "E") (pinfunction "E_E") (pintype "passive"))
      (node (ref "R2") (pin "2") (pinfunction "2_2") (pintype "passive"))
    )
    (net (code "79") (name "Net-(R8-Pad1)") (class "Default")
      (node (ref "R8") (pin "1") (pinfunction "1_1") (pintype "passive"))
      (node (ref "T1") (pin "G") (pinfunction "G_G") (pintype "passive"))
    )
    (net (code "80") (name "Net-(R9-Pad1)") (class "Default")
      (node (ref "R9") (pin "1") (pinfunction "1_1") (pintype "passive"))
      (node (ref "T2") (pin "G") (pinfunction "G_G") (pintype "passive"))
    )
    (net (code "81") (name "Net-(R10-Pad1)") (class "Default")
      (node (ref "R10") (pin "1") (pinfunction "1_1") (pintype "passive"))
      (node (ref "T3") (pin "G") (pinfunction "G_G") (pintype "passive"))
    )
    (net (code "82") (name "Net-(R15-Pad1)") (class "Default")
      (node (ref "R15") (pin "1") (pinfunction "1_1") (pintype "passive"))
      (node (ref "T4") (pin "G") (pinfunction "G_G") (pintype "passive"))
    )
    (net (code "83") (name "Net-(R16-S)") (class "Default")
      (node (ref "POTI") (pin "2") (pinfunction "2_2") (pintype "passive"))
      (node (ref "R16") (pin "2") (pinfunction "S_2") (pintype "passive"))
    )
    (net (code "84") (name "Net-(SPEAKER-PadP$1)") (class "Default")
      (node (ref "SPEAKER") (pin "P$1") (pinfunction "P$1_P$1") (pintype "bidirectional"))
      (node (ref "SPK") (pin "2") (pinfunction "2_2") (pintype "passive"))
    )
    (net (code "85") (name "Net-(U$3-VCC)") (class "Default")
      (node (ref "D2") (pin "A") (pinfunction "A_A") (pintype "passive"))
      (node (ref "LSP5") (pin "MP") (pinfunction "MP_MP") (pintype "passive"))
      (node (ref "U$3") (pin "2") (pinfunction "VCC_2") (pintype "bidirectional"))
    )
    (net (code "86") (name "Net-(USB-D+)") (class "Default")
      (node (ref "D3") (pin "C") (pinfunction "C_C") (pintype "passive"))
      (node (ref "R12") (pin "1") (pinfunction "1_1") (pintype "passive"))
      (node (ref "R14") (pin "2") (pinfunction "2_2") (pintype "passive"))
      (node (ref "USB") (pin "3") (pinfunction "D+_3") (pintype "passive"))
    )
    (net (code "87") (name "Net-(USB-D-)") (class "Default")
      (node (ref "D4") (pin "C") (pinfunction "C_C") (pintype "passive"))
      (node (ref "R11") (pin "1") (pinfunction "1_1") (pintype "passive"))
      (node (ref "R13") (pin "2") (pinfunction "2_2") (pintype "passive"))
      (node (ref "USB") (pin "2") (pinfunction "D-_2") (pintype "passive"))
    )
    (net (code "88") (name "Net-(USB-SHLD1)") (class "Default")
      (node (ref "SJ1") (pin "2") (pinfunction "2_2") (pintype "passive"))
      (node (ref "USB") (pin "6") (pinfunction "SHLD1_6") (pintype "passive"))
      (node (ref "USB") (pin "7") (pinfunction "SHLD2_7") (pintype "passive"))
    )
    (net (code "89") (name "unconnected-(IC3A-R2OUT-Pad9)") (class "Default")
      (node (ref "IC3") (pin "9") (pinfunction "R2OUT_9") (pintype "output"))
    )
    (net (code "90") (name "unconnected-(IC3A-T2OUT-Pad7)") (class "Default")
      (node (ref "IC3") (pin "7") (pinfunction "T2OUT_7") (pintype "output"))
    )
    (net (code "91") (name "unconnected-(U$3-NO-Pad1)") (class "Default")
      (node (ref "U$3") (pin "1") (pinfunction "NO_1") (pintype "bidirectional"))
    )
  )
)
